# 1_Strain_Gauge_Board.net
KiCad netlist of a schematic drawn in EAGLE
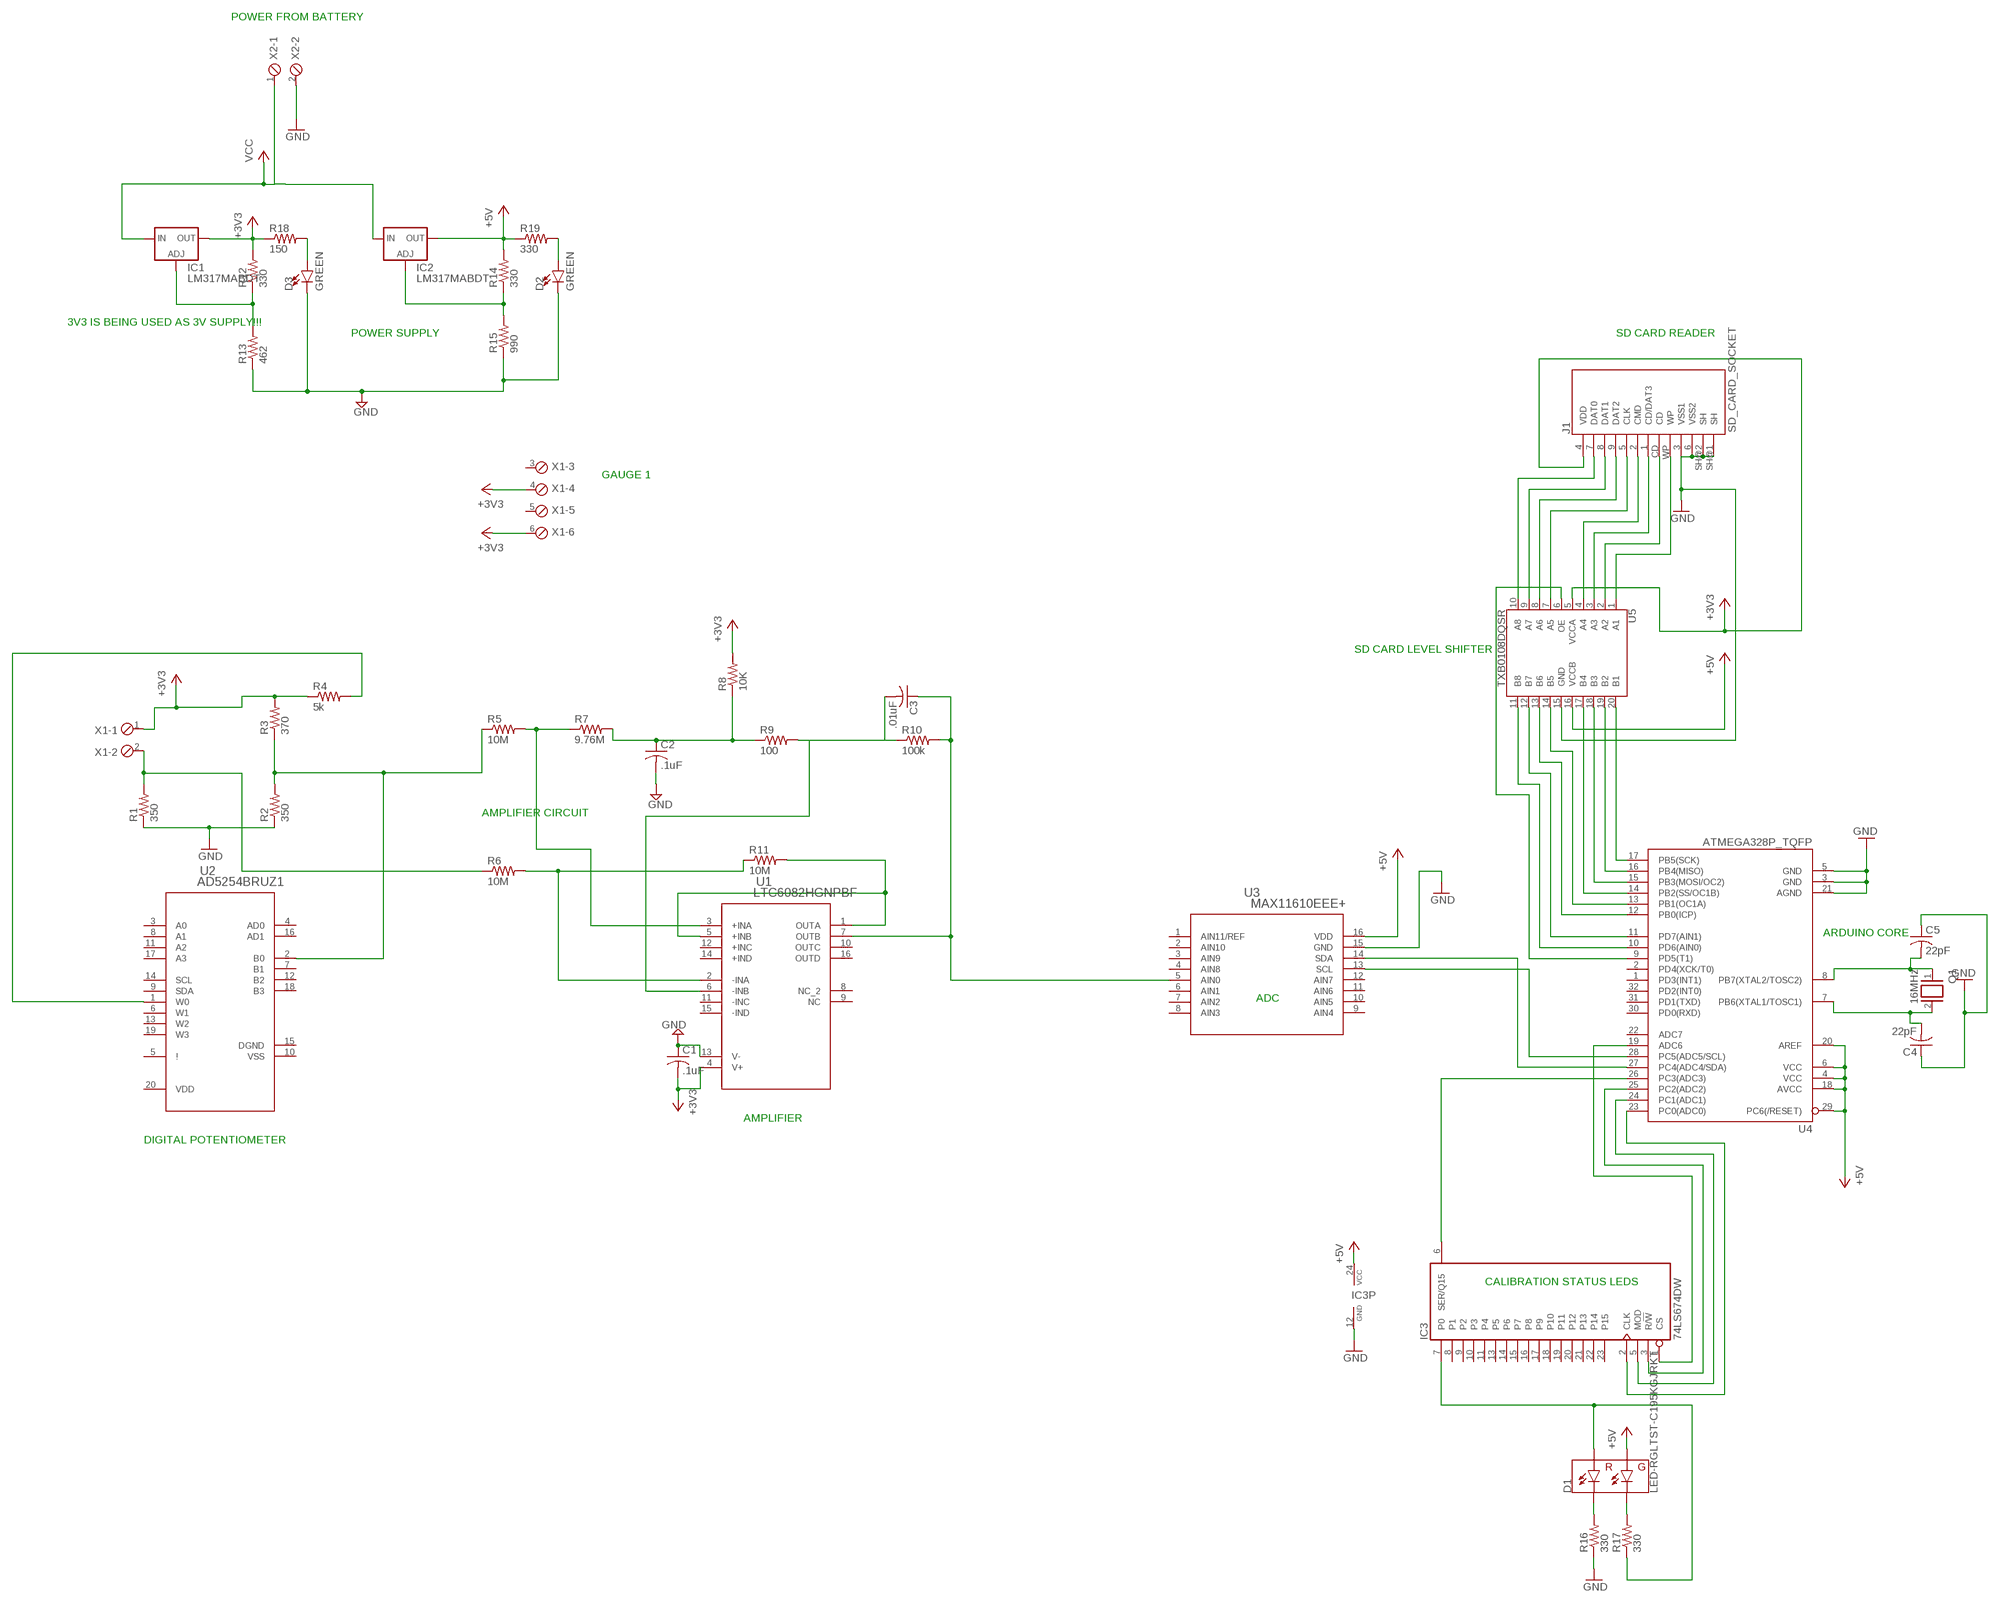
[diagram p0: schematic, sheet 1]

(export (version "E")
  (design (tool "Eeschema 10.0.6"))
  (components
    (comp (ref "C1")
      (value ".1uF")
      (footprint "eagle-import:C1206K")
      (libsource (lib "eagle-import") (part "C-USC1206K"))
    )
    (comp (ref "C2")
      (value ".1uF")
      (footprint "eagle-import:C1206K")
      (libsource (lib "eagle-import") (part "C-USC1206K"))
    )
    (comp (ref "C3")
      (value ".01uF")
      (footprint "eagle-import:C1206K")
      (libsource (lib "eagle-import") (part "C-USC1206K"))
    )
    (comp (ref "C4")
      (value "22pF")
      (footprint "eagle-import:C1206K")
      (libsource (lib "eagle-import") (part "C-USC1206K"))
    )
    (comp (ref "C5")
      (value "22pF")
      (footprint "eagle-import:C1206K")
      (libsource (lib "eagle-import") (part "C-USC1206K"))
    )
    (comp (ref "D1")
      (value "LED-RGLTST-C195KGJRKT")
      (footprint "eagle-import:LTST-C195KGJRKT")
      (libsource (lib "eagle-import") (part "LED-RGLTST-C195KGJRKT"))
    )
    (comp (ref "D2")
      (value "GREEN")
      (footprint "eagle-import:LED-1206")
      (libsource (lib "eagle-import") (part "LED-GREEN1206"))
    )
    (comp (ref "D3")
      (value "GREEN")
      (footprint "eagle-import:LED-1206")
      (libsource (lib "eagle-import") (part "LED-GREEN1206"))
    )
    (comp (ref "IC1")
      (value "LM317MABDT")
      (footprint "eagle-import:DPACK")
      (libsource (lib "eagle-import") (part "v-reg_409_LM317?MABDT"))
    )
    (comp (ref "IC2")
      (value "LM317MABDT")
      (footprint "eagle-import:DPACK")
      (libsource (lib "eagle-import") (part "v-reg_409_LM317?MABDT"))
    )
    (comp (ref "IC3")
      (value "74LS674DW")
      (footprint "eagle-import:SO24W")
      (libsource (lib "eagle-import") (part "74674DWLS"))
    )
    (comp (ref "J1")
      (value "SD_CARD_SOCKET")
      (footprint "eagle-import:SD")
      (libsource (lib "eagle-import") (part "SD_CARD_SOCKET"))
    )
    (comp (ref "Q1")
      (value "16MHz")
      (footprint "eagle-import:QS")
      (libsource (lib "eagle-import") (part "XTAL/S"))
    )
    (comp (ref "R1")
      (value "350")
      (footprint "eagle-import:M1206")
      (libsource (lib "eagle-import") (part "R-US_M1206"))
    )
    (comp (ref "R2")
      (value "350")
      (footprint "eagle-import:M1206")
      (libsource (lib "eagle-import") (part "R-US_M1206"))
    )
    (comp (ref "R3")
      (value "370")
      (footprint "eagle-import:M1206")
      (libsource (lib "eagle-import") (part "R-US_M1206"))
    )
    (comp (ref "R4")
      (value "5k")
      (footprint "eagle-import:M1206")
      (libsource (lib "eagle-import") (part "R-US_M1206"))
    )
    (comp (ref "R5")
      (value "10M")
      (footprint "eagle-import:M1206")
      (libsource (lib "eagle-import") (part "R-US_M1206"))
    )
    (comp (ref "R6")
      (value "10M")
      (footprint "eagle-import:M1206")
      (libsource (lib "eagle-import") (part "R-US_M1206"))
    )
    (comp (ref "R7")
      (value "9.76M")
      (footprint "eagle-import:M1206")
      (libsource (lib "eagle-import") (part "R-US_M1206"))
    )
    (comp (ref "R8")
      (value "10K")
      (footprint "eagle-import:M1206")
      (libsource (lib "eagle-import") (part "R-US_M1206"))
    )
    (comp (ref "R9")
      (value "100")
      (footprint "eagle-import:M1206")
      (libsource (lib "eagle-import") (part "R-US_M1206"))
    )
    (comp (ref "R10")
      (value "100k")
      (footprint "eagle-import:M1206")
      (libsource (lib "eagle-import") (part "R-US_M1206"))
    )
    (comp (ref "R11")
      (value "10M")
      (footprint "eagle-import:M1206")
      (libsource (lib "eagle-import") (part "R-US_M1206"))
    )
    (comp (ref "R12")
      (value "330")
      (footprint "eagle-import:M1206")
      (libsource (lib "eagle-import") (part "R-US_M1206"))
    )
    (comp (ref "R13")
      (value "462")
      (footprint "eagle-import:M1206")
      (libsource (lib "eagle-import") (part "R-US_M1206"))
    )
    (comp (ref "R14")
      (value "330")
      (footprint "eagle-import:M1206")
      (libsource (lib "eagle-import") (part "R-US_M1206"))
    )
    (comp (ref "R15")
      (value "990")
      (footprint "eagle-import:M1206")
      (libsource (lib "eagle-import") (part "R-US_M1206"))
    )
    (comp (ref "R16")
      (value "330")
      (footprint "eagle-import:M1206")
      (libsource (lib "eagle-import") (part "R-US_M1206"))
    )
    (comp (ref "R17")
      (value "330")
      (footprint "eagle-import:M1206")
      (libsource (lib "eagle-import") (part "R-US_M1206"))
    )
    (comp (ref "R18")
      (value "150")
      (footprint "eagle-import:M1206")
      (libsource (lib "eagle-import") (part "R-US_M1206"))
    )
    (comp (ref "R19")
      (value "330")
      (footprint "eagle-import:M1206")
      (libsource (lib "eagle-import") (part "R-US_M1206"))
    )
    (comp (ref "U1")
      (value "LTC6082HGNPBF")
      (footprint "eagle-import:SSOP-16_GN")
      (fields (field (name "MANUFACTURER_PART_NUMBER") "LTC6082HGN#PBF"))
      (libsource (lib "eagle-import") (part "LTC6082HGNPBF"))
    )
    (comp (ref "U2")
      (value "AD5254BRUZ1")
      (footprint "eagle-import:RU_20")
      (libsource (lib "eagle-import") (part "AD5254BRUZ1"))
    )
    (comp (ref "U3")
      (value "MAX11610EEE+")
      (footprint "eagle-import:21-0055H_16")
      (libsource (lib "eagle-import") (part "MAX11610EEE+"))
    )
    (comp (ref "U4")
      (value "ATMEGA328P_TQFP")
      (footprint "eagle-import:TQFP32-08")
      (libsource (lib "eagle-import") (part "ATMEGA328P_TQFP"))
    )
    (comp (ref "U5")
      (value "TXB0108DQSR")
      (footprint "eagle-import:UFDFN-20")
      (libsource (lib "eagle-import") (part "TXB0108"))
    )
    (comp (ref "X1")
      (value "MPT6")
      (footprint "eagle-import:6POL254")
      (libsource (lib "eagle-import") (part "MPT6"))
    )
    (comp (ref "X2")
      (value "MPT2")
      (footprint "eagle-import:2POL254")
      (libsource (lib "eagle-import") (part "MPT2"))
    )
  )
  (nets
    (net (code "1") (name "+3V3") (class "Default")
      (node (ref "C1") (pin "2") (pinfunction "2_2") (pintype "passive"))
      (node (ref "IC1") (pin "4") (pinfunction "OUT_4") (pintype "passive"))
      (node (ref "J1") (pin "4") (pinfunction "VDD_4") (pintype "power_in"))
      (node (ref "R12") (pin "2") (pinfunction "2_2") (pintype "passive"))
      (node (ref "R18") (pin "1") (pinfunction "1_1") (pintype "passive"))
      (node (ref "R3") (pin "2") (pinfunction "2_2") (pintype "passive"))
      (node (ref "R4") (pin "1") (pinfunction "1_1") (pintype "passive"))
      (node (ref "R8") (pin "2") (pinfunction "2_2") (pintype "passive"))
      (node (ref "U1") (pin "4") (pinfunction "V+_4") (pintype "power_in"))
      (node (ref "U5") (pin "5") (pinfunction "VCCA_5") (pintype "bidirectional"))
      (node (ref "X1") (pin "1") (pinfunction "1_1") (pintype "passive"))
      (node (ref "X1") (pin "4") (pinfunction "1_4") (pintype "passive"))
      (node (ref "X1") (pin "6") (pinfunction "1_6") (pintype "passive"))
    )
    (net (code "2") (name "+5V") (class "Default")
      (node (ref "D1") (pin "P$1") (pinfunction "GA_P$1") (pintype "passive"))
      (node (ref "IC2") (pin "4") (pinfunction "OUT_4") (pintype "passive"))
      (node (ref "IC3") (pin "24") (pinfunction "VCC_24") (pintype "power_in"))
      (node (ref "R14") (pin "2") (pinfunction "2_2") (pintype "passive"))
      (node (ref "R19") (pin "1") (pinfunction "1_1") (pintype "passive"))
      (node (ref "U3") (pin "16") (pinfunction "VDD_16") (pintype "power_in"))
      (node (ref "U4") (pin "18") (pinfunction "AVCC_18") (pintype "bidirectional"))
      (node (ref "U4") (pin "20") (pinfunction "AREF_20") (pintype "bidirectional"))
      (node (ref "U4") (pin "29") (pinfunction "PC6(/RESET)_29") (pintype "bidirectional"))
      (node (ref "U4") (pin "4") (pinfunction "VCC_4") (pintype "bidirectional"))
      (node (ref "U4") (pin "6") (pinfunction "VCC_6") (pintype "bidirectional"))
      (node (ref "U5") (pin "16") (pinfunction "VCCB_16") (pintype "bidirectional"))
    )
    (net (code "3") (name "/VDD") (class "Default")
      (node (ref "U2") (pin "20") (pinfunction "VDD_20") (pintype "power_in"))
    )
    (net (code "4") (name "/VSS") (class "Default")
      (node (ref "U2") (pin "10") (pinfunction "VSS_10") (pintype "power_in"))
    )
    (net (code "5") (name "GND") (class "Default")
      (node (ref "C1") (pin "1") (pinfunction "1_1") (pintype "passive"))
      (node (ref "C2") (pin "2") (pinfunction "2_2") (pintype "passive"))
      (node (ref "C4") (pin "1") (pinfunction "1_1") (pintype "passive"))
      (node (ref "C5") (pin "1") (pinfunction "1_1") (pintype "passive"))
      (node (ref "D2") (pin "C") (pinfunction "C_C") (pintype "passive"))
      (node (ref "D3") (pin "C") (pinfunction "C_C") (pintype "passive"))
      (node (ref "IC3") (pin "12") (pinfunction "GND_12") (pintype "power_in"))
      (node (ref "J1") (pin "3") (pinfunction "VSS1_3") (pintype "power_in"))
      (node (ref "J1") (pin "6") (pinfunction "VSS2_6") (pintype "power_in"))
      (node (ref "J1") (pin "SH@1") (pinfunction "SH_SH@1") (pintype "bidirectional"))
      (node (ref "J1") (pin "SH@2") (pinfunction "SH_SH@2") (pintype "bidirectional"))
      (node (ref "R1") (pin "1") (pinfunction "1_1") (pintype "passive"))
      (node (ref "R13") (pin "1") (pinfunction "1_1") (pintype "passive"))
      (node (ref "R15") (pin "1") (pinfunction "1_1") (pintype "passive"))
      (node (ref "R16") (pin "1") (pinfunction "1_1") (pintype "passive"))
      (node (ref "R2") (pin "1") (pinfunction "1_1") (pintype "passive"))
      (node (ref "U1") (pin "13") (pinfunction "V-_13") (pintype "power_in"))
      (node (ref "U3") (pin "15") (pinfunction "GND_15") (pintype "power_in"))
      (node (ref "U4") (pin "21") (pinfunction "AGND_21") (pintype "bidirectional"))
      (node (ref "U4") (pin "3") (pinfunction "GND_3") (pintype "bidirectional"))
      (node (ref "U4") (pin "5") (pinfunction "GND_5") (pintype "bidirectional"))
      (node (ref "U5") (pin "15") (pinfunction "GND_15") (pintype "bidirectional"))
      (node (ref "X2") (pin "2") (pinfunction "1_2") (pintype "passive"))
    )
    (net (code "6") (name "Net-(C2-Pad1)") (class "Default")
      (node (ref "C2") (pin "1") (pinfunction "1_1") (pintype "passive"))
      (node (ref "R7") (pin "2") (pinfunction "2_2") (pintype "passive"))
      (node (ref "R8") (pin "1") (pinfunction "1_1") (pintype "passive"))
      (node (ref "R9") (pin "1") (pinfunction "1_1") (pintype "passive"))
    )
    (net (code "7") (name "Net-(D1-GC)") (class "Default")
      (node (ref "D1") (pin "P$3") (pinfunction "GC_P$3") (pintype "passive"))
      (node (ref "R17") (pin "2") (pinfunction "2_2") (pintype "passive"))
    )
    (net (code "8") (name "Net-(D1-RA)") (class "Default")
      (node (ref "D1") (pin "P$2") (pinfunction "RA_P$2") (pintype "passive"))
      (node (ref "IC3") (pin "7") (pinfunction "P0_7") (pintype "input"))
      (node (ref "R17") (pin "1") (pinfunction "1_1") (pintype "passive"))
    )
    (net (code "9") (name "Net-(D1-RC)") (class "Default")
      (node (ref "D1") (pin "P$4") (pinfunction "RC_P$4") (pintype "passive"))
      (node (ref "R16") (pin "2") (pinfunction "2_2") (pintype "passive"))
    )
    (net (code "10") (name "Net-(D2-PadA)") (class "Default")
      (node (ref "D2") (pin "A") (pinfunction "A_A") (pintype "passive"))
      (node (ref "R19") (pin "2") (pinfunction "2_2") (pintype "passive"))
    )
    (net (code "11") (name "Net-(D3-PadA)") (class "Default")
      (node (ref "D3") (pin "A") (pinfunction "A_A") (pintype "passive"))
      (node (ref "R18") (pin "2") (pinfunction "2_2") (pintype "passive"))
    )
    (net (code "12") (name "Net-(IC1-ADJ)") (class "Default")
      (node (ref "IC1") (pin "1") (pinfunction "ADJ_1") (pintype "input"))
      (node (ref "R12") (pin "1") (pinfunction "1_1") (pintype "passive"))
      (node (ref "R13") (pin "2") (pinfunction "2_2") (pintype "passive"))
    )
    (net (code "13") (name "Net-(IC2-ADJ)") (class "Default")
      (node (ref "IC2") (pin "1") (pinfunction "ADJ_1") (pintype "input"))
      (node (ref "R14") (pin "1") (pinfunction "1_1") (pintype "passive"))
      (node (ref "R15") (pin "2") (pinfunction "2_2") (pintype "passive"))
    )
    (net (code "14") (name "Net-(IC3A-CLK)") (class "Default")
      (node (ref "IC3") (pin "2") (pinfunction "CLK_2") (pintype "input"))
      (node (ref "U4") (pin "23") (pinfunction "PC0(ADC0)_23") (pintype "bidirectional"))
    )
    (net (code "15") (name "Net-(IC3A-CS)") (class "Default")
      (node (ref "IC3") (pin "1") (pinfunction "CS_1") (pintype "input"))
      (node (ref "U4") (pin "19") (pinfunction "ADC6_19") (pintype "bidirectional"))
    )
    (net (code "16") (name "Net-(IC3A-MOD)") (class "Default")
      (node (ref "IC3") (pin "5") (pinfunction "MOD_5") (pintype "input"))
      (node (ref "U4") (pin "24") (pinfunction "PC1(ADC1)_24") (pintype "bidirectional"))
    )
    (net (code "17") (name "Net-(IC3A-R{slash}~{W})") (class "Default")
      (node (ref "IC3") (pin "3") (pinfunction "R/~{W}_3") (pintype "input"))
      (node (ref "U4") (pin "25") (pinfunction "PC2(ADC2)_25") (pintype "bidirectional"))
    )
    (net (code "18") (name "Net-(IC3A-SER{slash}Q15)") (class "Default")
      (node (ref "IC3") (pin "6") (pinfunction "SER/Q15_6") (pintype "bidirectional"))
      (node (ref "U4") (pin "26") (pinfunction "PC3(ADC3)_26") (pintype "bidirectional"))
    )
    (net (code "19") (name "Net-(J1-CD{slash}DAT3)") (class "Default")
      (node (ref "J1") (pin "1") (pinfunction "CD/DAT3_1") (pintype "bidirectional"))
      (node (ref "U5") (pin "3") (pinfunction "A3_3") (pintype "bidirectional"))
    )
    (net (code "20") (name "Net-(J1-CLK)") (class "Default")
      (node (ref "J1") (pin "5") (pinfunction "CLK_5") (pintype "bidirectional"))
      (node (ref "U5") (pin "7") (pinfunction "A5_7") (pintype "bidirectional"))
    )
    (net (code "21") (name "Net-(J1-CMD)") (class "Default")
      (node (ref "J1") (pin "2") (pinfunction "CMD_2") (pintype "bidirectional"))
      (node (ref "U5") (pin "4") (pinfunction "A4_4") (pintype "bidirectional"))
    )
    (net (code "22") (name "Net-(J1-DAT0)") (class "Default")
      (node (ref "J1") (pin "7") (pinfunction "DAT0_7") (pintype "bidirectional"))
      (node (ref "U5") (pin "10") (pinfunction "A8_10") (pintype "bidirectional"))
    )
    (net (code "23") (name "Net-(J1-DAT1)") (class "Default")
      (node (ref "J1") (pin "8") (pinfunction "DAT1_8") (pintype "bidirectional"))
      (node (ref "U5") (pin "9") (pinfunction "A7_9") (pintype "bidirectional"))
    )
    (net (code "24") (name "Net-(J1-DAT2)") (class "Default")
      (node (ref "J1") (pin "9") (pinfunction "DAT2_9") (pintype "bidirectional"))
      (node (ref "U5") (pin "8") (pinfunction "A6_8") (pintype "bidirectional"))
    )
    (net (code "25") (name "Net-(U1-+INA)") (class "Default")
      (node (ref "R5") (pin "2") (pinfunction "2_2") (pintype "passive"))
      (node (ref "R7") (pin "1") (pinfunction "1_1") (pintype "passive"))
      (node (ref "U1") (pin "3") (pinfunction "+INA_3") (pintype "input"))
    )
    (net (code "26") (name "Net-(U1-+INB)") (class "Default")
      (node (ref "R11") (pin "2") (pinfunction "2_2") (pintype "passive"))
      (node (ref "U1") (pin "1") (pinfunction "OUTA_1") (pintype "output"))
      (node (ref "U1") (pin "5") (pinfunction "+INB_5") (pintype "input"))
    )
    (net (code "27") (name "Net-(U1--INA)") (class "Default")
      (node (ref "R11") (pin "1") (pinfunction "1_1") (pintype "passive"))
      (node (ref "R6") (pin "2") (pinfunction "2_2") (pintype "passive"))
      (node (ref "U1") (pin "2") (pinfunction "-INA_2") (pintype "input"))
    )
    (net (code "28") (name "Net-(U1--INB)") (class "Default")
      (node (ref "C3") (pin "2") (pinfunction "2_2") (pintype "passive"))
      (node (ref "R10") (pin "1") (pinfunction "1_1") (pintype "passive"))
      (node (ref "R9") (pin "2") (pinfunction "2_2") (pintype "passive"))
      (node (ref "U1") (pin "6") (pinfunction "-INB_6") (pintype "input"))
    )
    (net (code "29") (name "Net-(U1-OUTB)") (class "Default")
      (node (ref "C3") (pin "1") (pinfunction "1_1") (pintype "passive"))
      (node (ref "R10") (pin "2") (pinfunction "2_2") (pintype "passive"))
      (node (ref "U1") (pin "7") (pinfunction "OUTB_7") (pintype "output"))
      (node (ref "U3") (pin "5") (pinfunction "AIN0_5") (pintype "input"))
    )
    (net (code "30") (name "Net-(U2-B0)") (class "Default")
      (node (ref "R2") (pin "2") (pinfunction "2_2") (pintype "passive"))
      (node (ref "R3") (pin "1") (pinfunction "1_1") (pintype "passive"))
      (node (ref "R5") (pin "1") (pinfunction "1_1") (pintype "passive"))
      (node (ref "U2") (pin "2") (pinfunction "B0_2") (pintype "passive"))
    )
    (net (code "31") (name "Net-(U2-W0)") (class "Default")
      (node (ref "R4") (pin "2") (pinfunction "2_2") (pintype "passive"))
      (node (ref "U2") (pin "1") (pinfunction "W0_1") (pintype "passive"))
    )
    (net (code "32") (name "Net-(U3-SCL)") (class "Default")
      (node (ref "U3") (pin "13") (pinfunction "SCL_13") (pintype "input"))
      (node (ref "U4") (pin "28") (pinfunction "PC5(ADC5/SCL)_28") (pintype "bidirectional"))
    )
    (net (code "33") (name "Net-(U3-SDA)") (class "Default")
      (node (ref "U3") (pin "14") (pinfunction "SDA_14") (pintype "bidirectional"))
      (node (ref "U4") (pin "27") (pinfunction "PC4(ADC4/SDA)_27") (pintype "bidirectional"))
    )
    (net (code "34") (name "Net-(U4-PB0(ICP))") (class "Default")
      (node (ref "U4") (pin "12") (pinfunction "PB0(ICP)_12") (pintype "bidirectional"))
      (node (ref "U5") (pin "13") (pinfunction "B6_13") (pintype "bidirectional"))
    )
    (net (code "35") (name "Net-(U4-PB1(OC1A))") (class "Default")
      (node (ref "U4") (pin "13") (pinfunction "PB1(OC1A)_13") (pintype "bidirectional"))
      (node (ref "U5") (pin "14") (pinfunction "B5_14") (pintype "bidirectional"))
    )
    (net (code "36") (name "Net-(U4-PB2(SS{slash}OC1B))") (class "Default")
      (node (ref "U4") (pin "14") (pinfunction "PB2(SS/OC1B)_14") (pintype "bidirectional"))
      (node (ref "U5") (pin "17") (pinfunction "B4_17") (pintype "bidirectional"))
    )
    (net (code "37") (name "Net-(U4-PB3(MOSI{slash}OC2))") (class "Default")
      (node (ref "U4") (pin "15") (pinfunction "PB3(MOSI/OC2)_15") (pintype "bidirectional"))
      (node (ref "U5") (pin "18") (pinfunction "B3_18") (pintype "bidirectional"))
    )
    (net (code "38") (name "Net-(U4-PB4(MISO))") (class "Default")
      (node (ref "U4") (pin "16") (pinfunction "PB4(MISO)_16") (pintype "bidirectional"))
      (node (ref "U5") (pin "19") (pinfunction "B2_19") (pintype "bidirectional"))
    )
    (net (code "39") (name "Net-(U4-PB5(SCK))") (class "Default")
      (node (ref "U4") (pin "17") (pinfunction "PB5(SCK)_17") (pintype "bidirectional"))
      (node (ref "U5") (pin "20") (pinfunction "B1_20") (pintype "bidirectional"))
    )
    (net (code "40") (name "Net-(U4-PB6(XTAL1{slash}TOSC1))") (class "Default")
      (node (ref "C4") (pin "2") (pinfunction "2_2") (pintype "passive"))
      (node (ref "Q1") (pin "2") (pinfunction "2_2") (pintype "passive"))
      (node (ref "U4") (pin "7") (pinfunction "PB6(XTAL1/TOSC1)_7") (pintype "bidirectional"))
    )
    (net (code "41") (name "Net-(U4-PB7(XTAL2{slash}TOSC2))") (class "Default")
      (node (ref "C5") (pin "2") (pinfunction "2_2") (pintype "passive"))
      (node (ref "Q1") (pin "1") (pinfunction "1_1") (pintype "passive"))
      (node (ref "U4") (pin "8") (pinfunction "PB7(XTAL2/TOSC2)_8") (pintype "bidirectional"))
    )
    (net (code "42") (name "Net-(U4-PD5(T1))") (class "Default")
      (node (ref "U4") (pin "9") (pinfunction "PD5(T1)_9") (pintype "bidirectional"))
      (node (ref "U5") (pin "6") (pinfunction "OE_6") (pintype "bidirectional"))
    )
    (net (code "43") (name "Net-(U4-PD6(AIN0))") (class "Default")
      (node (ref "U4") (pin "10") (pinfunction "PD6(AIN0)_10") (pintype "bidirectional"))
      (node (ref "U5") (pin "11") (pinfunction "B8_11") (pintype "bidirectional"))
    )
    (net (code "44") (name "Net-(U4-PD7(AIN1))") (class "Default")
      (node (ref "U4") (pin "11") (pinfunction "PD7(AIN1)_11") (pintype "bidirectional"))
      (node (ref "U5") (pin "12") (pinfunction "B7_12") (pintype "bidirectional"))
    )
    (net (code "45") (name "Net-(U5-A1)") (class "Default")
      (node (ref "J1") (pin "WP") (pinfunction "WP_WP") (pintype "bidirectional"))
      (node (ref "U5") (pin "1") (pinfunction "A1_1") (pintype "bidirectional"))
    )
    (net (code "46") (name "Net-(U5-A2)") (class "Default")
      (node (ref "J1") (pin "CD") (pinfunction "CD_CD") (pintype "bidirectional"))
      (node (ref "U5") (pin "2") (pinfunction "A2_2") (pintype "bidirectional"))
    )
    (net (code "47") (name "Net-(X1B-1)") (class "Default")
      (node (ref "R1") (pin "2") (pinfunction "2_2") (pintype "passive"))
      (node (ref "R6") (pin "1") (pinfunction "1_1") (pintype "passive"))
      (node (ref "X1") (pin "2") (pinfunction "1_2") (pintype "passive"))
    )
    (net (code "48") (name "VCC") (class "Default")
      (node (ref "IC1") (pin "3") (pinfunction "IN_3") (pintype "input"))
      (node (ref "IC2") (pin "3") (pinfunction "IN_3") (pintype "input"))
      (node (ref "X2") (pin "1") (pinfunction "1_1") (pintype "passive"))
    )
    (net (code "49") (name "unconnected-(IC3A-P1-Pad8)") (class "Default")
      (node (ref "IC3") (pin "8") (pinfunction "P1_8") (pintype "input"))
    )
    (net (code "50") (name "unconnected-(IC3A-P2-Pad9)") (class "Default")
      (node (ref "IC3") (pin "9") (pinfunction "P2_9") (pintype "input"))
    )
    (net (code "51") (name "unconnected-(IC3A-P3-Pad10)") (class "Default")
      (node (ref "IC3") (pin "10") (pinfunction "P3_10") (pintype "input"))
    )
    (net (code "52") (name "unconnected-(IC3A-P4-Pad11)") (class "Default")
      (node (ref "IC3") (pin "11") (pinfunction "P4_11") (pintype "input"))
    )
    (net (code "53") (name "unconnected-(IC3A-P5-Pad13)") (class "Default")
      (node (ref "IC3") (pin "13") (pinfunction "P5_13") (pintype "input"))
    )
    (net (code "54") (name "unconnected-(IC3A-P6-Pad14)") (class "Default")
      (node (ref "IC3") (pin "14") (pinfunction "P6_14") (pintype "input"))
    )
    (net (code "55") (name "unconnected-(IC3A-P7-Pad15)") (class "Default")
      (node (ref "IC3") (pin "15") (pinfunction "P7_15") (pintype "input"))
    )
    (net (code "56") (name "unconnected-(IC3A-P8-Pad16)") (class "Default")
      (node (ref "IC3") (pin "16") (pinfunction "P8_16") (pintype "input"))
    )
    (net (code "57") (name "unconnected-(IC3A-P9-Pad17)") (class "Default")
      (node (ref "IC3") (pin "17") (pinfunction "P9_17") (pintype "input"))
    )
    (net (code "58") (name "unconnected-(IC3A-P10-Pad18)") (class "Default")
      (node (ref "IC3") (pin "18") (pinfunction "P10_18") (pintype "input"))
    )
    (net (code "59") (name "unconnected-(IC3A-P11-Pad19)") (class "Default")
      (node (ref "IC3") (pin "19") (pinfunction "P11_19") (pintype "input"))
    )
    (net (code "60") (name "unconnected-(IC3A-P12-Pad20)") (class "Default")
      (node (ref "IC3") (pin "20") (pinfunction "P12_20") (pintype "input"))
    )
    (net (code "61") (name "unconnected-(IC3A-P13-Pad21)") (class "Default")
      (node (ref "IC3") (pin "21") (pinfunction "P13_21") (pintype "input"))
    )
    (net (code "62") (name "unconnected-(IC3A-P14-Pad22)") (class "Default")
      (node (ref "IC3") (pin "22") (pinfunction "P14_22") (pintype "input"))
    )
    (net (code "63") (name "unconnected-(IC3A-P15-Pad23)") (class "Default")
      (node (ref "IC3") (pin "23") (pinfunction "P15_23") (pintype "input"))
    )
    (net (code "64") (name "unconnected-(U1-+INC-Pad12)") (class "Default")
      (node (ref "U1") (pin "12") (pinfunction "+INC_12") (pintype "input"))
    )
    (net (code "65") (name "unconnected-(U1-+IND-Pad14)") (class "Default")
      (node (ref "U1") (pin "14") (pinfunction "+IND_14") (pintype "input"))
    )
    (net (code "66") (name "unconnected-(U1--INC-Pad11)") (class "Default")
      (node (ref "U1") (pin "11") (pinfunction "-INC_11") (pintype "input"))
    )
    (net (code "67") (name "unconnected-(U1--IND-Pad15)") (class "Default")
      (node (ref "U1") (pin "15") (pinfunction "-IND_15") (pintype "input"))
    )
    (net (code "68") (name "unconnected-(U1-NC-Pad9)") (class "Default")
      (node (ref "U1") (pin "9") (pinfunction "NC_9") (pintype "no_connect"))
    )
    (net (code "69") (name "unconnected-(U1-NC_2-Pad8)") (class "Default")
      (node (ref "U1") (pin "8") (pinfunction "NC_2_8") (pintype "no_connect"))
    )
    (net (code "70") (name "unconnected-(U1-OUTC-Pad10)") (class "Default")
      (node (ref "U1") (pin "10") (pinfunction "OUTC_10") (pintype "output"))
    )
    (net (code "71") (name "unconnected-(U1-OUTD-Pad16)") (class "Default")
      (node (ref "U1") (pin "16") (pinfunction "OUTD_16") (pintype "output"))
    )
    (net (code "72") (name "unconnected-(U2-A0-Pad3)") (class "Default")
      (node (ref "U2") (pin "3") (pinfunction "A0_3") (pintype "passive"))
    )
    (net (code "73") (name "unconnected-(U2-A1-Pad8)") (class "Default")
      (node (ref "U2") (pin "8") (pinfunction "A1_8") (pintype "passive"))
    )
    (net (code "74") (name "unconnected-(U2-A2-Pad11)") (class "Default")
      (node (ref "U2") (pin "11") (pinfunction "A2_11") (pintype "passive"))
    )
    (net (code "75") (name "unconnected-(U2-A3-Pad17)") (class "Default")
      (node (ref "U2") (pin "17") (pinfunction "A3_17") (pintype "passive"))
    )
    (net (code "76") (name "unconnected-(U2-AD0-Pad4)") (class "Default")
      (node (ref "U2") (pin "4") (pinfunction "AD0_4") (pintype "passive"))
    )
    (net (code "77") (name "unconnected-(U2-AD1-Pad16)") (class "Default")
      (node (ref "U2") (pin "16") (pinfunction "AD1_16") (pintype "passive"))
    )
    (net (code "78") (name "unconnected-(U2-B1-Pad7)") (class "Default")
      (node (ref "U2") (pin "7") (pinfunction "B1_7") (pintype "passive"))
    )
    (net (code "79") (name "unconnected-(U2-B2-Pad12)") (class "Default")
      (node (ref "U2") (pin "12") (pinfunction "B2_12") (pintype "passive"))
    )
    (net (code "80") (name "unconnected-(U2-B3-Pad18)") (class "Default")
      (node (ref "U2") (pin "18") (pinfunction "B3_18") (pintype "passive"))
    )
    (net (code "81") (name "unconnected-(U2-DGND-Pad15)") (class "Default")
      (node (ref "U2") (pin "15") (pinfunction "DGND_15") (pintype "passive"))
    )
    (net (code "82") (name "unconnected-(U2-SCL-Pad14)") (class "Default")
      (node (ref "U2") (pin "14") (pinfunction "SCL_14") (pintype "passive"))
    )
    (net (code "83") (name "unconnected-(U2-SDA-Pad9)") (class "Default")
      (node (ref "U2") (pin "9") (pinfunction "SDA_9") (pintype "passive"))
    )
    (net (code "84") (name "unconnected-(U2-W1-Pad6)") (class "Default")
      (node (ref "U2") (pin "6") (pinfunction "W1_6") (pintype "passive"))
    )
    (net (code "85") (name "unconnected-(U2-W2-Pad13)") (class "Default")
      (node (ref "U2") (pin "13") (pinfunction "W2_13") (pintype "passive"))
    )
    (net (code "86") (name "unconnected-(U2-W3-Pad19)") (class "Default")
      (node (ref "U2") (pin "19") (pinfunction "W3_19") (pintype "passive"))
    )
    (net (code "87") (name "unconnected-(U2-~-Pad5)") (class "Default")
      (node (ref "U2") (pin "5") (pinfunction "~_5") (pintype "passive"))
    )
    (net (code "88") (name "unconnected-(U3-AIN1-Pad6)") (class "Default")
      (node (ref "U3") (pin "6") (pinfunction "AIN1_6") (pintype "input"))
    )
    (net (code "89") (name "unconnected-(U3-AIN2-Pad7)") (class "Default")
      (node (ref "U3") (pin "7") (pinfunction "AIN2_7") (pintype "input"))
    )
    (net (code "90") (name "unconnected-(U3-AIN3-Pad8)") (class "Default")
      (node (ref "U3") (pin "8") (pinfunction "AIN3_8") (pintype "input"))
    )
    (net (code "91") (name "unconnected-(U3-AIN4-Pad9)") (class "Default")
      (node (ref "U3") (pin "9") (pinfunction "AIN4_9") (pintype "input"))
    )
    (net (code "92") (name "unconnected-(U3-AIN5-Pad10)") (class "Default")
      (node (ref "U3") (pin "10") (pinfunction "AIN5_10") (pintype "input"))
    )
    (net (code "93") (name "unconnected-(U3-AIN6-Pad11)") (class "Default")
      (node (ref "U3") (pin "11") (pinfunction "AIN6_11") (pintype "input"))
    )
    (net (code "94") (name "unconnected-(U3-AIN7-Pad12)") (class "Default")
      (node (ref "U3") (pin "12") (pinfunction "AIN7_12") (pintype "input"))
    )
    (net (code "95") (name "unconnected-(U3-AIN8-Pad4)") (class "Default")
      (node (ref "U3") (pin "4") (pinfunction "AIN8_4") (pintype "input"))
    )
    (net (code "96") (name "unconnected-(U3-AIN9-Pad3)") (class "Default")
      (node (ref "U3") (pin "3") (pinfunction "AIN9_3") (pintype "input"))
    )
    (net (code "97") (name "unconnected-(U3-AIN10-Pad2)") (class "Default")
      (node (ref "U3") (pin "2") (pinfunction "AIN10_2") (pintype "input"))
    )
    (net (code "98") (name "unconnected-(U3-AIN11{slash}REF-Pad1)") (class "Default")
      (node (ref "U3") (pin "1") (pinfunction "AIN11/REF_1") (pintype "bidirectional"))
    )
    (net (code "99") (name "unconnected-(U4-ADC7-Pad22)") (class "Default")
      (node (ref "U4") (pin "22") (pinfunction "ADC7_22") (pintype "bidirectional"))
    )
    (net (code "100") (name "unconnected-(U4-PD0(RXD)-Pad30)") (class "Default")
      (node (ref "U4") (pin "30") (pinfunction "PD0(RXD)_30") (pintype "bidirectional"))
    )
    (net (code "101") (name "unconnected-(U4-PD1(TXD)-Pad31)") (class "Default")
      (node (ref "U4") (pin "31") (pinfunction "PD1(TXD)_31") (pintype "bidirectional"))
    )
    (net (code "102") (name "unconnected-(U4-PD2(INT0)-Pad32)") (class "Default")
      (node (ref "U4") (pin "32") (pinfunction "PD2(INT0)_32") (pintype "bidirectional"))
    )
    (net (code "103") (name "unconnected-(U4-PD3(INT1)-Pad1)") (class "Default")
      (node (ref "U4") (pin "1") (pinfunction "PD3(INT1)_1") (pintype "bidirectional"))
    )
    (net (code "104") (name "unconnected-(U4-PD4(XCK{slash}T0)-Pad2)") (class "Default")
      (node (ref "U4") (pin "2") (pinfunction "PD4(XCK/T0)_2") (pintype "bidirectional"))
    )
    (net (code "105") (name "unconnected-(X1C-1-Pad3)") (class "Default")
      (node (ref "X1") (pin "3") (pinfunction "1_3") (pintype "passive"))
    )
    (net (code "106") (name "unconnected-(X1E-1-Pad5)") (class "Default")
      (node (ref "X1") (pin "5") (pinfunction "1_5") (pintype "passive"))
    )
  )
)
